# LED.net
KiCad netlist of a schematic drawn in Altium Designer
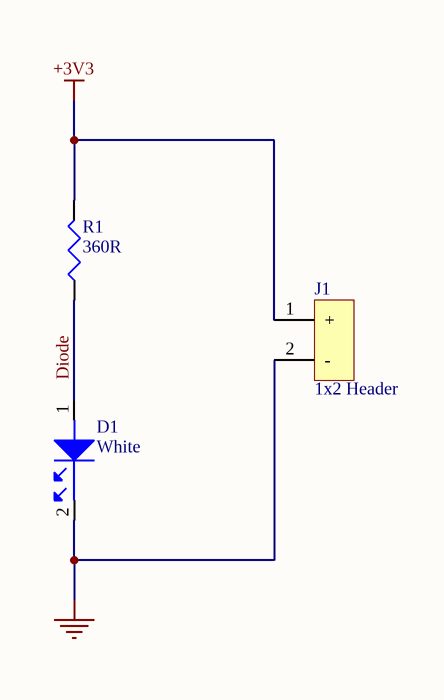
[diagram p0: LED.SchDoc]

(export (version "E")
  (design (tool "Eeschema 10.0.6"))
  (components
    (comp (ref "D1")
      (value "White")
      (footprint "LED0603w")
      (description "PANASONIC - LNJ037X8ARA - LED WHITE HIGH BRIGHT ESS SMD")
      (fields
        (field (name "MANUFACTURER") "Panasonic SSG")
        (field (name "MANUFACTURER PART NUMBER") "LNJ037X8ARA")
      )
      (libsource (lib "LED_Schlib") (part "LNJ037X8ARA"))
    )
    (comp (ref "J1")
      (value "1x2 Header")
      (footprint "Header1x2")
      (description "Conn Wire to Board HDR 2 POS 2.54mm Solder ST Thru-Hole Bag")
      (fields (field (name "MANUFACTURER") "Molex") (field (name "MANUFACTURER PART NUMBER") "22-29-2021"))
      (libsource (lib "LED_Schlib") (part "22-29-2021"))
    )
    (comp (ref "R1")
      (value "360R")
      (footprint "R0805")
      (description "Res Thick Film 0805 360 Ohm 1% 0.125W(1/8W) ±100ppm/C Molded SMD Automotive Paper T/R")
      (fields
        (field (name "MANUFACTURER") "Vishay")
        (field (name "MANUFACTURER PART NUMBER") "CRCW0805360RFKEA")
      )
      (libsource (lib "LED_Schlib") (part "CRCW0805360RFKEA"))
    )
  )
  (nets
    (net (code "1") (name "+3V3") (class "Default")
      (node (ref "J1") (pin "1") (pinfunction "+_1") (pintype "passive"))
      (node (ref "R1") (pin "3") (pinfunction "3_3") (pintype "passive"))
    )
    (net (code "2") (name "/Diode") (class "Default")
      (node (ref "D1") (pin "1") (pinfunction "1_1") (pintype "passive"))
      (node (ref "R1") (pin "4") (pinfunction "4_4") (pintype "passive"))
    )
    (net (code "3") (name "GND") (class "Default")
      (node (ref "D1") (pin "2") (pinfunction "2_2") (pintype "passive"))
      (node (ref "J1") (pin "2") (pinfunction "-_2") (pintype "passive"))
    )
  )
)
